# Input_power.net
KiCad netlist of a schematic drawn in Altium Designer
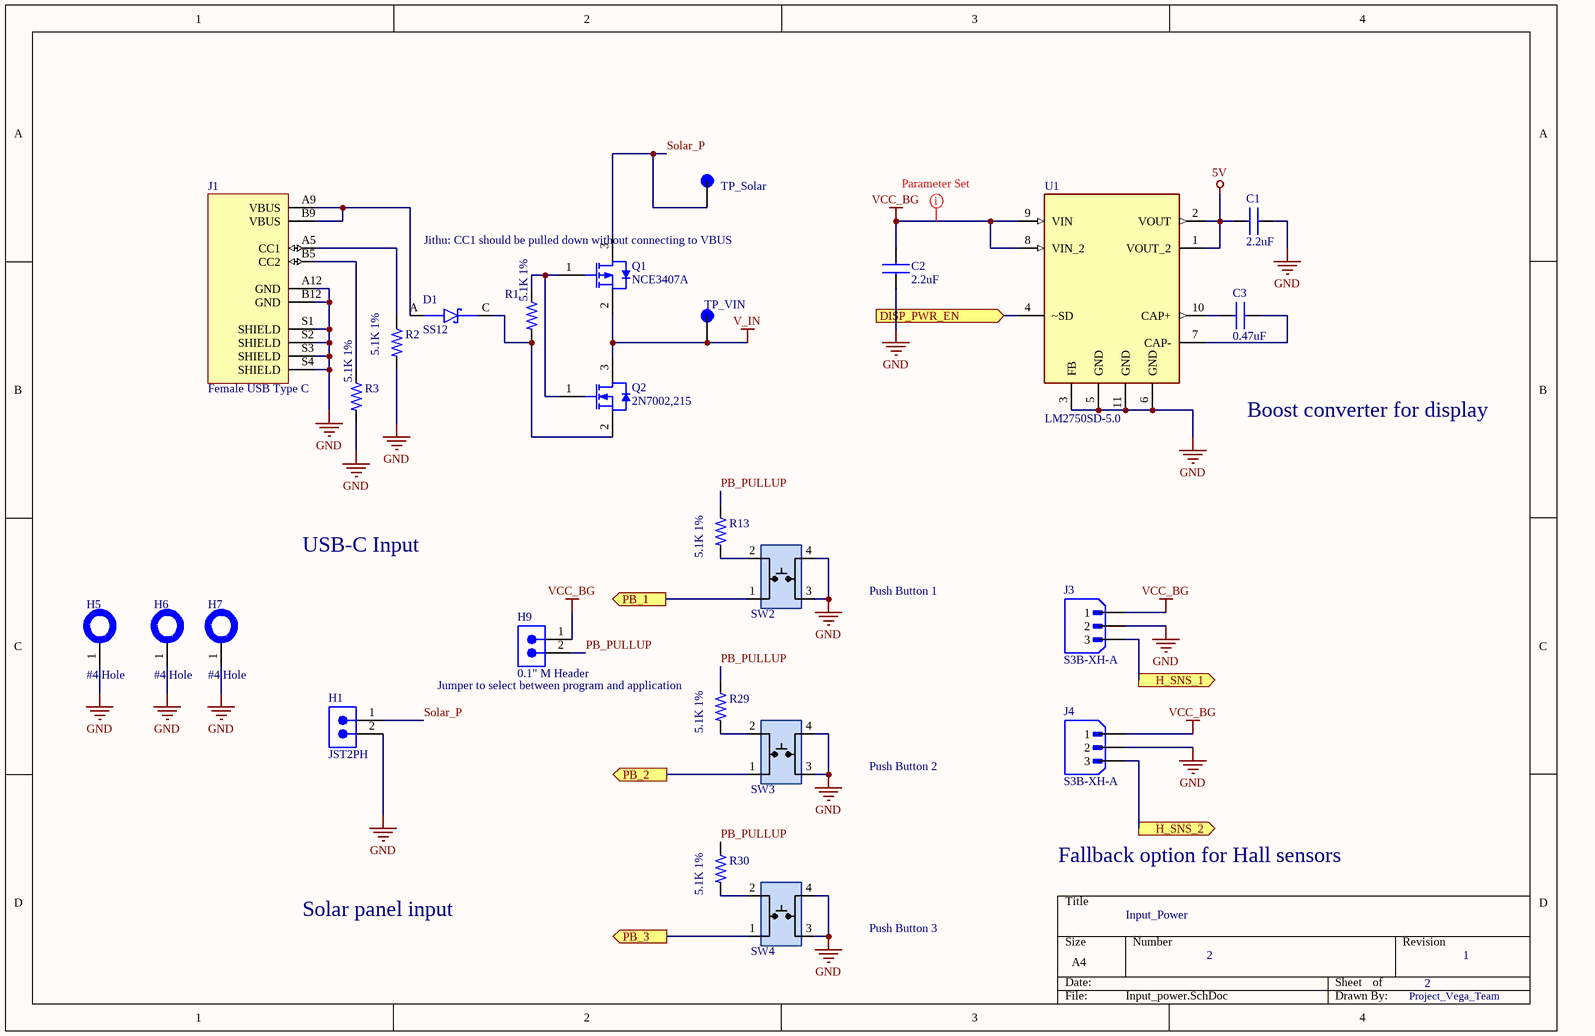
[diagram p0: Input_power.SchDoc]

(export (version "E")
  (design (tool "Eeschema 10.0.6"))
  (components
    (comp (ref "C1")
      (value "2.2uF")
      (footprint "CAP_0603_1MM")
      (fields
        (field (name "MANUFACTURER") "Murata")
        (field (name "MANUFACTURER PART NUMBER") "GRM188R61A226ME15D")
        (field (name "TOLERANCE") "20 %")
      )
      (libsource (lib "LPEDT_Parts") (part "GRM188R61A226ME15D"))
    )
    (comp (ref "C2")
      (value "2.2uF")
      (footprint "CAP_0603_1MM")
      (description "CAP CER 22UF 10V X5R 0603")
      (fields
        (field (name "MANUFACTURER") "Murata")
        (field (name "MANUFACTURER PART NUMBER") "GRM188R61A226ME15D")
      )
      (libsource (lib "LPEDT_Parts") (part "GRM188R61A226ME15D"))
    )
    (comp (ref "C3")
      (value "0.47uF")
      (footprint "CAP_0603_1MM")
      (description "CAP CER 22UF 10V X5R 0603")
      (fields
        (field (name "MANUFACTURER") "Murata")
        (field (name "MANUFACTURER PART NUMBER") "GRM188R61A226ME15D")
      )
      (libsource (lib "LPEDT_Parts") (part "GRM188R61A226ME15D"))
    )
    (comp (ref "D1")
      (value "SS12")
      (footprint "DIOM4427X270N")
      (description "DIODE SCHOTTKY 20V 1A DO214AC")
      (fields (field (name "MF") "Klein Tools,"))
      (libsource (lib "Project_Vega") (part "SS12"))
    )
    (comp (ref "H1")
      (value "JST2PH")
      (footprint "JST_B2B-PH-K-S(LF)(SN)")
      (description "Connector Header Through Hole 2 position 0.079\" (2.00mm)")
      (fields (field (name "MANUFACTURER") "JST") (field (name "MANUFACTURER PART NUMBER") "B2B-PH-K-S"))
      (libsource (lib "Connectors") (part "JST2PH"))
    )
    (comp (ref "H5")
      (value "#4 Hole")
      (footprint "HOLE_#4")
      (libsource (lib "Project_Vega") (part "HOLE_#4"))
    )
    (comp (ref "H6")
      (value "#4 Hole")
      (footprint "HOLE_#4")
      (libsource (lib "Project_Vega") (part "HOLE_#4"))
    )
    (comp (ref "H7")
      (value "#4 Hole")
      (footprint "HOLE_#4")
      (libsource (lib "Project_Vega") (part "HOLE_#4"))
    )
    (comp (ref "H9")
      (value "0.1\" M Header")
      (footprint "2-PIN_MALE_HEADER_01-IN")
      (description "CONN HEADER VERT 2POS 2.54MM")
      (fields
        (field (name "MANUFACTURER") "Sullins")
        (field (name "MANUFACTURER PART NUMBER") "PRPC002SAAN-RC")
      )
      (libsource (lib "Connectors") (part "PRPC002SAAN-RC"))
    )
    (comp (ref "J1")
      (value "Female USB Type C")
      (footprint "GCT_USB4125-GF-A_REVA2")
      (description "USB Connector, 24 Contact(s), Female, Right Angle, Solder Terminal, Locking, Receptacle")
      (fields
        (field (name "MANUFACTURER PART NUMBER") "USB4125-GF-A_REVA2")
        (field (name "MANUFACTURER") "Global Connector Technology")
      )
      (libsource (lib "Project_Vega") (part "USB-C Power Connector"))
    )
    (comp (ref "J3")
      (value "S3B-XH-A")
      (footprint "JST_S3B-XH-A")
      (description "Board Connector, 3 Contact(s), 1 Row(s), Male, Right Angle, Solder Terminal")
      (fields (field (name "MF") "JST Sales") (field (name "MP") "B3B-XH-A(LF)(SN)"))
      (libsource (lib "Project_Vega") (part "S3B-XH-A"))
    )
    (comp (ref "J4")
      (value "S3B-XH-A")
      (footprint "JST_S3B-XH-A")
      (description "Board Connector, 3 Contact(s), 1 Row(s), Male, Right Angle, Solder Terminal")
      (fields (field (name "MF") "JST Sales") (field (name "MP") "B3B-XH-A(LF)(SN)"))
      (libsource (lib "Project_Vega") (part "S3B-XH-A"))
    )
    (comp (ref "Q1")
      (value "NCE3407A")
      (footprint "NCEP-SOT23-3_M")
      (fields (field (name "MANUFACTURER") "NCE Power"))
      (libsource (lib "University of Colorado Boulder") (part "PEMOS-GSD-3"))
    )
    (comp (ref "Q2")
      (value "2N7002,215")
      (footprint "NXP-SOT23-3_V")
      (fields (field (name "POWER") "830mW") (field (name "MANUFACTURER") "NXP Semiconductors"))
      (libsource (lib "University of Colorado Boulder") (part "NEMOS-GSD-3"))
    )
    (comp (ref "R1")
      (value "5.1K 1%")
      (footprint "RES_0603_1608X06")
      (description "SMD Chip Resistor, 5.1KOhm, ± 1%, 100 mW, 0603 [1608 Metric], Thick Film, General Purpose")
      (fields
        (field (name "MANUFACTURER") "Yageo")
        (field (name "MANUFACTURER PART NUMBER") "RC0603FR-07316KL")
      )
      (libsource (lib "LPEDT_Parts") (part "RC0603FR-07316KL"))
    )
    (comp (ref "R2")
      (value "5.1K 1%")
      (footprint "RES_0603_1608X06")
      (description "SMD Chip Resistor, 316 kOhm, ± 1%, 100 mW, 0603 [1608 Metric], Thick Film, General Purpose")
      (fields
        (field (name "MANUFACTURER") "Yageo")
        (field (name "MANUFACTURER PART NUMBER") "RC0603FR-07316KL")
      )
      (libsource (lib "LPEDT_Parts") (part "RC0603FR-07316KL"))
    )
    (comp (ref "R3")
      (value "5.1K 1%")
      (footprint "RES_0603_1608X06")
      (description "SMD Chip Resistor, 5.1KOhm, ± 1%, 100 mW, 0603 [1608 Metric], Thick Film, General Purpose")
      (fields
        (field (name "MANUFACTURER") "Yageo")
        (field (name "MANUFACTURER PART NUMBER") "RC0603FR-07316KL")
      )
      (libsource (lib "LPEDT_Parts") (part "RC0603FR-07316KL"))
    )
    (comp (ref "R13")
      (value "5.1K 1%")
      (footprint "RES_0603")
      (description "SMD Chip Resistor, 5.1KOhm, ± 1%, 100 mW, 0603 [1608 Metric], Thick Film, General Purpose")
      (fields
        (field (name "MANUFACTURER") "Yageo")
        (field (name "MANUFACTURER PART NUMBER") "RC0603FR-07316KL")
      )
      (libsource (lib "LPEDT_Parts") (part "RC0603FR-07316KL"))
    )
    (comp (ref "R29")
      (value "5.1K 1%")
      (footprint "RES_0603")
      (description "SMD Chip Resistor, 5.1KOhm, ± 1%, 100 mW, 0603 [1608 Metric], Thick Film, General Purpose")
      (fields
        (field (name "MANUFACTURER") "Yageo")
        (field (name "MANUFACTURER PART NUMBER") "RC0603FR-07316KL")
      )
      (libsource (lib "LPEDT_Parts") (part "RC0603FR-07316KL"))
    )
    (comp (ref "R30")
      (value "5.1K 1%")
      (footprint "RES_0603")
      (description "SMD Chip Resistor, 5.1KOhm, ± 1%, 100 mW, 0603 [1608 Metric], Thick Film, General Purpose")
      (fields
        (field (name "MANUFACTURER") "Yageo")
        (field (name "MANUFACTURER PART NUMBER") "RC0603FR-07316KL")
      )
      (libsource (lib "LPEDT_Parts") (part "RC0603FR-07316KL"))
    )
    (comp (ref "SW2")
      (value "TL3305AF160QG")
      (footprint "Switch_JLC")
      (description "Tactile Switch SPST-NO Top Actuated Surface Mount")
      (fields (field (name "MFR PART #") "KH-4.5X4.5X4.3H-STM") (field (name "LCSC PART#") "C2837550"))
      (libsource (lib "ECEN5730Lib_2023_05_DS") (part "SW_Push_Button_JLC"))
    )
    (comp (ref "SW3")
      (value "TL3305AF160QG")
      (footprint "Switch_JLC")
      (description "Tactile Switch SPST-NO Top Actuated Surface Mount")
      (fields (field (name "MFR PART #") "KH-4.5X4.5X4.3H-STM") (field (name "LCSC PART#") "C2837550"))
      (libsource (lib "ECEN5730Lib_2023_05_DS") (part "SW_Push_Button_JLC"))
    )
    (comp (ref "SW4")
      (value "TL3305AF160QG")
      (footprint "Switch_JLC")
      (description "Tactile Switch SPST-NO Top Actuated Surface Mount")
      (fields (field (name "MFR PART #") "KH-4.5X4.5X4.3H-STM") (field (name "LCSC PART#") "C2837550"))
      (libsource (lib "ECEN5730Lib_2023_05_DS") (part "SW_Push_Button_JLC"))
    )
    (comp (ref "TP_Solar")
      (value "Test_point")
      (footprint "1")
      (description "SMT Test Point- Mininature-1000 pc Reels")
      (fields (field (name "MP") "5019") (field (name "MF") "Keystone Electronics"))
      (libsource (lib "Project_Vega") (part "Test_point"))
    )
    (comp (ref "TP_VIN")
      (value "Test_point")
      (footprint "1")
      (description "SMT Test Point- Mininature-1000 pc Reels")
      (fields (field (name "MP") "5019") (field (name "MF") "Keystone Electronics"))
      (libsource (lib "Project_Vega") (part "Test_point"))
    )
    (comp (ref "U1")
      (value "LM2750SD-5.0")
      (footprint "LM2750_DFN300X300X80-11N")
      (description "Voltage Regulators - Switching Regulators Reg Switch Capacitor Boost Reg")
      (fields (field (name "MP") "LM2750SD-5-0") (field (name "MANUFACTURER") "TI National Semiconductor"))
      (libsource (lib "Project_Vega") (part "LM2750SD-5.0"))
    )
  )
  (nets
    (net (code "1") (name "/DISP_PWR_EN") (class "Default")
      (node (ref "U1") (pin "4") (pinfunction "~SD_4") (pintype "passive"))
    )
    (net (code "2") (name "/H_SNS_1") (class "Default")
      (node (ref "J3") (pin "3") (pinfunction "3_3") (pintype "passive"))
    )
    (net (code "3") (name "/H_SNS_2") (class "Default")
      (node (ref "J4") (pin "3") (pinfunction "3_3") (pintype "passive"))
    )
    (net (code "4") (name "/PB_1") (class "Default")
      (node (ref "SW2") (pin "1") (pinfunction "1_1") (pintype "passive"))
    )
    (net (code "5") (name "/PB_2") (class "Default")
      (node (ref "SW3") (pin "1") (pinfunction "1_1") (pintype "passive"))
    )
    (net (code "6") (name "/PB_3") (class "Default")
      (node (ref "SW4") (pin "1") (pinfunction "1_1") (pintype "passive"))
    )
    (net (code "7") (name "/PB_PULLUP") (class "Default")
      (node (ref "H9") (pin "2") (pinfunction "2_2") (pintype "passive"))
      (node (ref "R13") (pin "1") (pinfunction "1_1") (pintype "passive"))
      (node (ref "R29") (pin "1") (pinfunction "1_1") (pintype "passive"))
      (node (ref "R30") (pin "1") (pinfunction "1_1") (pintype "passive"))
    )
    (net (code "8") (name "/Solar_P") (class "Default")
      (node (ref "H1") (pin "1") (pinfunction "1_1") (pintype "passive"))
      (node (ref "Q1") (pin "3") (pinfunction "DRAIN_3") (pintype "passive"))
      (node (ref "TP_Solar") (pin "TP") (pinfunction "Solar_TP") (pintype "passive"))
    )
    (net (code "9") (name "5V") (class "Default")
      (node (ref "C1") (pin "2") (pinfunction "2_2") (pintype "passive"))
      (node (ref "U1") (pin "1") (pinfunction "VOUT_2_1") (pintype "passive"))
      (node (ref "U1") (pin "2") (pinfunction "VOUT_2") (pintype "output"))
    )
    (net (code "10") (name "GND") (class "Default")
      (node (ref "C1") (pin "1") (pinfunction "1_1") (pintype "passive"))
      (node (ref "C2") (pin "1") (pinfunction "1_1") (pintype "passive"))
      (node (ref "H1") (pin "2") (pinfunction "2_2") (pintype "passive"))
      (node (ref "H5") (pin "1") (pinfunction "1_1") (pintype "passive"))
      (node (ref "H6") (pin "1") (pinfunction "1_1") (pintype "passive"))
      (node (ref "H7") (pin "1") (pinfunction "1_1") (pintype "passive"))
      (node (ref "J1") (pin "A12") (pinfunction "GND_A12") (pintype "passive"))
      (node (ref "J1") (pin "B12") (pinfunction "GND_B12") (pintype "passive"))
      (node (ref "J1") (pin "S1") (pinfunction "SHIELD_S1") (pintype "passive"))
      (node (ref "J1") (pin "S2") (pinfunction "SHIELD_S2") (pintype "passive"))
      (node (ref "J1") (pin "S3") (pinfunction "SHIELD_S3") (pintype "passive"))
      (node (ref "J1") (pin "S4") (pinfunction "SHIELD_S4") (pintype "passive"))
      (node (ref "J3") (pin "2") (pinfunction "2_2") (pintype "passive"))
      (node (ref "J4") (pin "2") (pinfunction "2_2") (pintype "passive"))
      (node (ref "R2") (pin "2") (pinfunction "2_2") (pintype "passive"))
      (node (ref "R3") (pin "2") (pinfunction "2_2") (pintype "passive"))
      (node (ref "SW2") (pin "3") (pinfunction "3_3") (pintype "passive"))
      (node (ref "SW2") (pin "4") (pinfunction "4_4") (pintype "passive"))
      (node (ref "SW3") (pin "3") (pinfunction "3_3") (pintype "passive"))
      (node (ref "SW3") (pin "4") (pinfunction "4_4") (pintype "passive"))
      (node (ref "SW4") (pin "3") (pinfunction "3_3") (pintype "passive"))
      (node (ref "SW4") (pin "4") (pinfunction "4_4") (pintype "passive"))
      (node (ref "U1") (pin "11") (pinfunction "GND_11") (pintype "passive"))
      (node (ref "U1") (pin "3") (pinfunction "FB_3") (pintype "passive"))
      (node (ref "U1") (pin "5") (pinfunction "GND_5") (pintype "passive"))
      (node (ref "U1") (pin "6") (pinfunction "GND_6") (pintype "passive"))
    )
    (net (code "11") (name "Net-(D1-PadA)") (class "Default")
      (node (ref "D1") (pin "A") (pinfunction "A_A") (pintype "passive"))
      (node (ref "J1") (pin "A9") (pinfunction "VBUS_A9") (pintype "power_in"))
      (node (ref "J1") (pin "B9") (pinfunction "VBUS_B9") (pintype "power_in"))
    )
    (net (code "12") (name "Net-(J1-CC1)") (class "Default")
      (node (ref "J1") (pin "A5") (pinfunction "CC1_A5") (pintype "bidirectional"))
      (node (ref "R2") (pin "1") (pinfunction "1_1") (pintype "passive"))
    )
    (net (code "13") (name "Net-(J1-CC2)") (class "Default")
      (node (ref "J1") (pin "B5") (pinfunction "CC2_B5") (pintype "bidirectional"))
      (node (ref "R3") (pin "1") (pinfunction "1_1") (pintype "passive"))
    )
    (net (code "14") (name "Net-(Q1-GATE)") (class "Default")
      (node (ref "Q1") (pin "1") (pinfunction "GATE_1") (pintype "passive"))
      (node (ref "Q2") (pin "1") (pinfunction "G_1") (pintype "passive"))
      (node (ref "R1") (pin "1") (pinfunction "1_1") (pintype "passive"))
    )
    (net (code "15") (name "Net-(Q2-S)") (class "Default")
      (node (ref "D1") (pin "C") (pinfunction "C_C") (pintype "passive"))
      (node (ref "Q2") (pin "2") (pinfunction "S_2") (pintype "passive"))
      (node (ref "R1") (pin "2") (pinfunction "2_2") (pintype "passive"))
    )
    (net (code "16") (name "Net-(R13-Pad2)") (class "Default")
      (node (ref "R13") (pin "2") (pinfunction "2_2") (pintype "passive"))
      (node (ref "SW2") (pin "2") (pinfunction "2_2") (pintype "passive"))
    )
    (net (code "17") (name "Net-(R29-Pad2)") (class "Default")
      (node (ref "R29") (pin "2") (pinfunction "2_2") (pintype "passive"))
      (node (ref "SW3") (pin "2") (pinfunction "2_2") (pintype "passive"))
    )
    (net (code "18") (name "Net-(R30-Pad2)") (class "Default")
      (node (ref "R30") (pin "2") (pinfunction "2_2") (pintype "passive"))
      (node (ref "SW4") (pin "2") (pinfunction "2_2") (pintype "passive"))
    )
    (net (code "19") (name "Net-(U1-CAP+)") (class "Default")
      (node (ref "C3") (pin "2") (pinfunction "2_2") (pintype "passive"))
      (node (ref "U1") (pin "10") (pinfunction "CAP+_10") (pintype "output"))
    )
    (net (code "20") (name "Net-(U1-CAP-)") (class "Default")
      (node (ref "C3") (pin "1") (pinfunction "1_1") (pintype "passive"))
      (node (ref "U1") (pin "7") (pinfunction "CAP-_7") (pintype "passive"))
    )
    (net (code "21") (name "VCC_BG") (class "Default")
      (node (ref "C2") (pin "2") (pinfunction "2_2") (pintype "passive"))
      (node (ref "H9") (pin "1") (pinfunction "1_1") (pintype "passive"))
      (node (ref "J3") (pin "1") (pinfunction "1_1") (pintype "passive"))
      (node (ref "J4") (pin "1") (pinfunction "1_1") (pintype "passive"))
      (node (ref "U1") (pin "8") (pinfunction "VIN_2_8") (pintype "input"))
      (node (ref "U1") (pin "9") (pinfunction "VIN_9") (pintype "input"))
    )
    (net (code "22") (name "V_IN") (class "Default")
      (node (ref "Q1") (pin "2") (pinfunction "SOURCE_2") (pintype "passive"))
      (node (ref "Q2") (pin "3") (pinfunction "D_3") (pintype "passive"))
      (node (ref "TP_VIN") (pin "TP") (pinfunction "Solar_TP") (pintype "passive"))
    )
  )
)
